# ProPrj_LED__2025-12-14-09-51-38.net
KiCad netlist of a schematic drawn in EasyEDA Pro
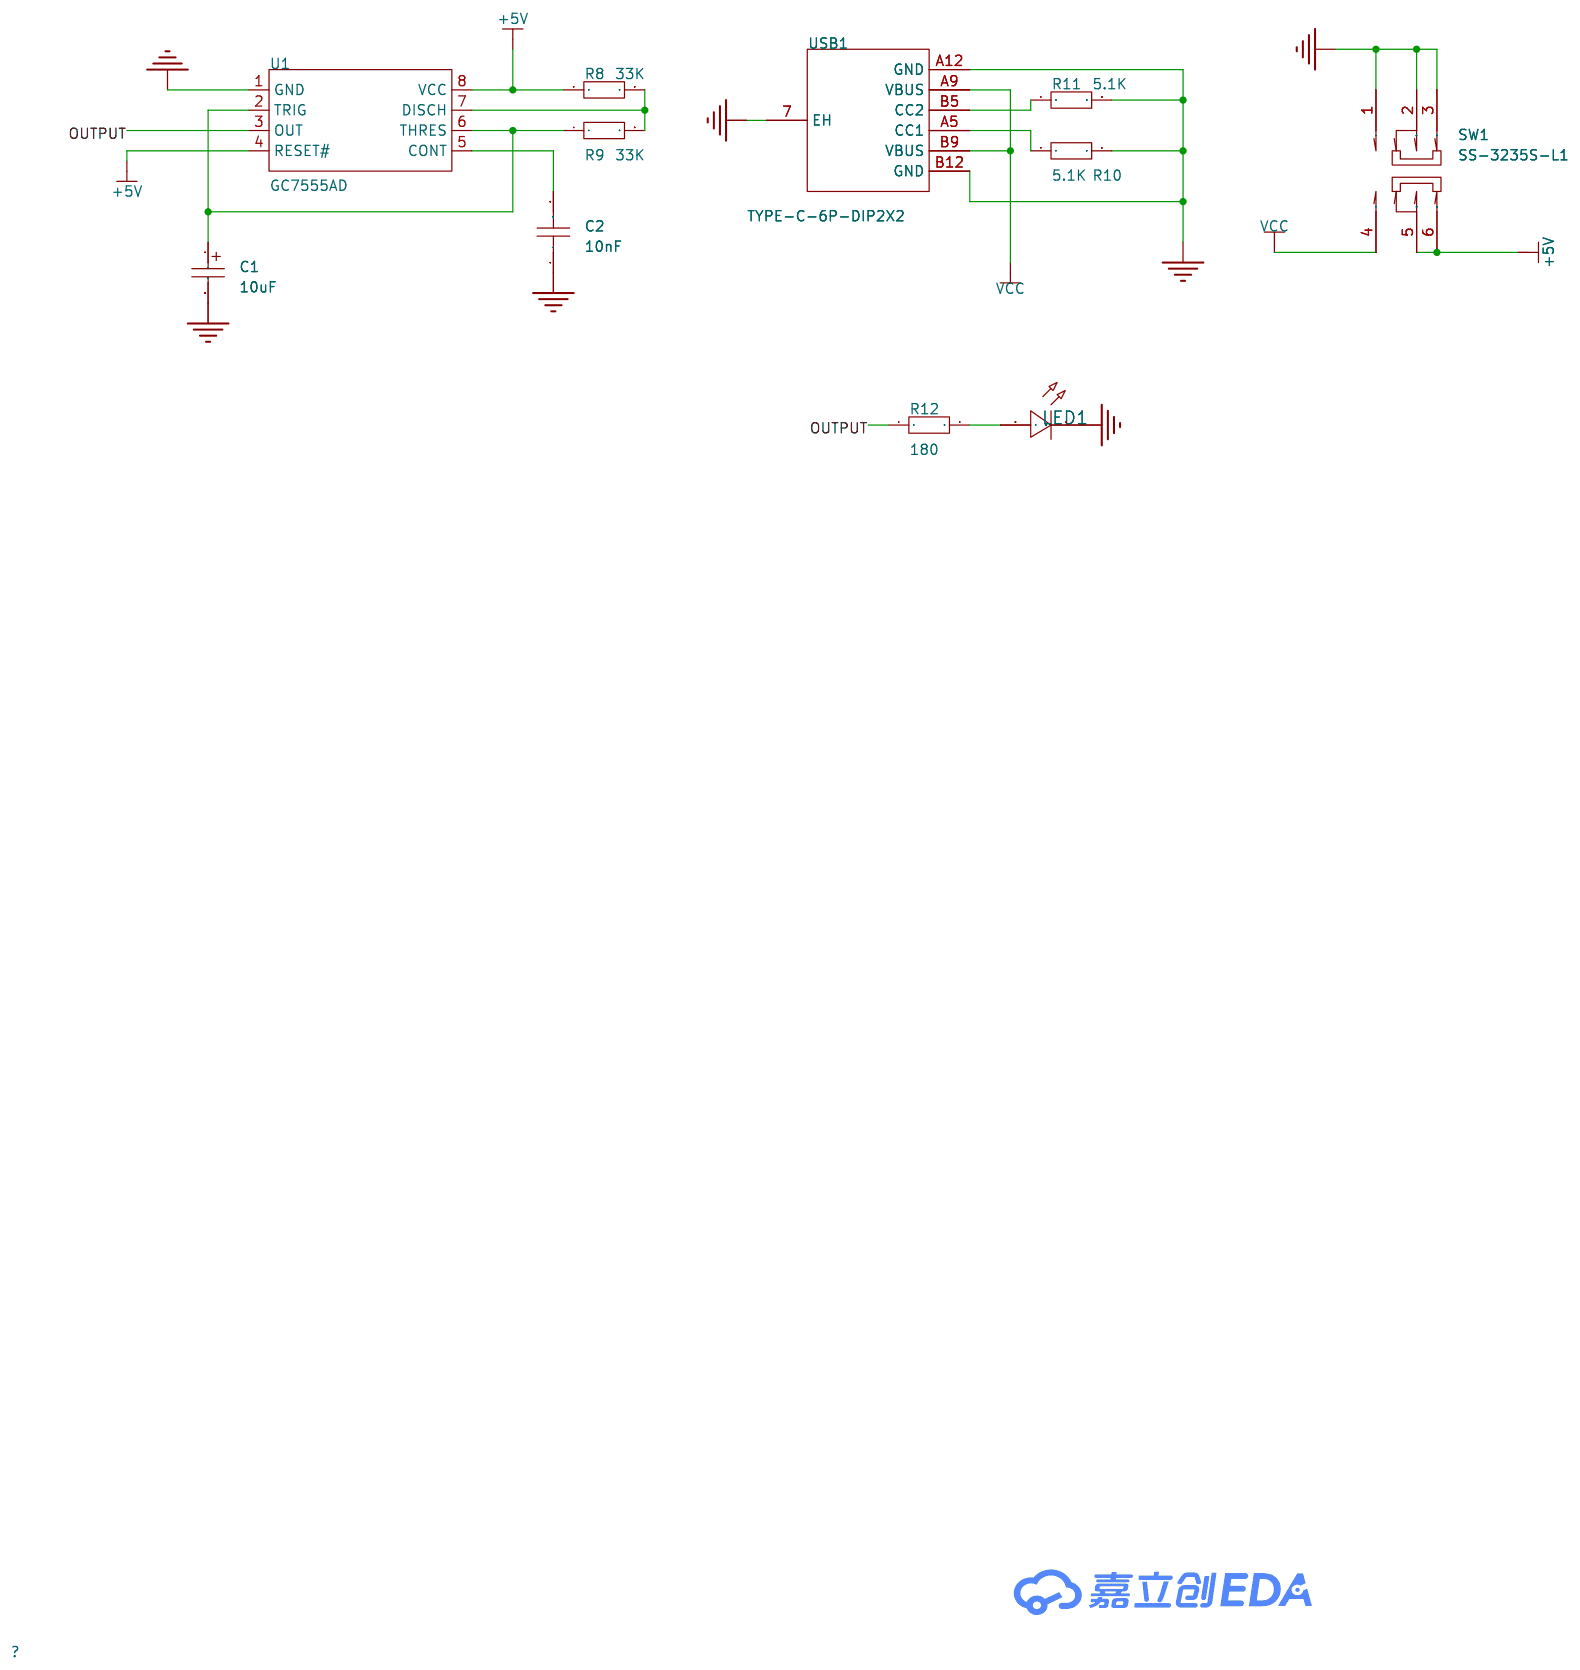
[diagram p0: schematic sheet]

(export (version "E")
  (design (tool "Eeschema 10.0.6"))
  (components
    (comp (ref "C1")
      (value "10uF")
      (footprint "easyedapro:C_Ele_SMD_3x5.4mm")
      (libsource (lib "easyedapro") (part "CAP"))
    )
    (comp (ref "C2")
      (value "10nF")
      (footprint "easyedapro:C0603")
      (libsource (lib "easyedapro") (part "Capacitance"))
    )
    (comp (ref "LED1")
      (value "~")
      (footprint "easyedapro:LED_0603")
      (libsource (lib "easyedapro") (part "LED_R"))
    )
    (comp (ref "R8") (value "33K") (footprint "easyedapro:R0805") (libsource (lib "easyedapro") (part "电阻")))
    (comp (ref "R9") (value "33K") (footprint "easyedapro:R0805") (libsource (lib "easyedapro") (part "电阻")))
    (comp (ref "R10")
      (value "5.1K")
      (footprint "easyedapro:R0805")
      (libsource (lib "easyedapro") (part "电阻"))
    )
    (comp (ref "R11")
      (value "5.1K")
      (footprint "easyedapro:R0805")
      (libsource (lib "easyedapro") (part "电阻"))
    )
    (comp (ref "R12") (value "180") (footprint "easyedapro:R0805") (libsource (lib "easyedapro") (part "电阻")))
    (comp (ref "SW1")
      (value "SS-3235S-L1")
      (footprint "easyedapro:SW-SMD_SS-3235S-LX")
      (description "电路结构:双刀双掷;安装方式:卧贴;开关颜色:黑色;额定电流:50mA;额定电压:12V;工作寿命:1万次;")
      (fields (field (name "Manufacturer") "XKB Connection(中国星坤)"))
      (libsource (lib "easyedapro") (part "SS-3235S-L1"))
    )
    (comp (ref "U1")
      (value "GC7555AD")
      (footprint "easyedapro:PDIP-8_L9.5-W6.4-P2.54-LS7.6-BL")
      (description "通用计时器：时基电路；计时；脉冲产生；满足用户（至少工业级）自主可控的需求。")
      (fields (field (name "Manufacturer") "Sungine(双竞集成)"))
      (libsource (lib "easyedapro") (part "GC7555AD"))
    )
    (comp (ref "USB1")
      (value "TYPE-C-6P-DIP2X2")
      (footprint "easyedapro:TYPE-C-SMD_TYPE-C-6P")
      (libsource (lib "easyedapro") (part "TYPE-C-6P-DIP2X2"))
    )
  )
  (nets
    (net (code "1") (name "+5V") (class "Default")
      (node (ref "R8") (pin "1") (pinfunction "1_1") (pintype "input"))
      (node (ref "SW1") (pin "5") (pinfunction "5_5") (pintype "unspecified"))
      (node (ref "SW1") (pin "6") (pinfunction "6_6") (pintype "unspecified"))
      (node (ref "U1") (pin "4") (pinfunction "RESET#_4") (pintype "unspecified"))
      (node (ref "U1") (pin "8") (pinfunction "VCC_8") (pintype "unspecified"))
    )
    (net (code "2") (name "/OUTPUT") (class "Default")
      (node (ref "R12") (pin "1") (pinfunction "1_1") (pintype "input"))
      (node (ref "U1") (pin "3") (pinfunction "OUT_3") (pintype "unspecified"))
    )
    (net (code "3") (name "GND") (class "Default")
      (node (ref "C1") (pin "2") (pinfunction "2_2") (pintype "input"))
      (node (ref "C2") (pin "1") (pinfunction "1_1") (pintype "input"))
      (node (ref "LED1") (pin "1") (pinfunction "C_1") (pintype "input"))
      (node (ref "R10") (pin "2") (pinfunction "2_2") (pintype "input"))
      (node (ref "R11") (pin "2") (pinfunction "2_2") (pintype "input"))
      (node (ref "SW1") (pin "1") (pinfunction "1_1") (pintype "unspecified"))
      (node (ref "SW1") (pin "2") (pinfunction "2_2") (pintype "unspecified"))
      (node (ref "SW1") (pin "3") (pinfunction "3_3") (pintype "unspecified"))
      (node (ref "U1") (pin "1") (pinfunction "GND_1") (pintype "unspecified"))
      (node (ref "USB1") (pin "7") (pinfunction "EH_7") (pintype "unspecified"))
      (node (ref "USB1") (pin "A12") (pinfunction "GND_A12") (pintype "unspecified"))
      (node (ref "USB1") (pin "B12") (pinfunction "GND_B12") (pintype "unspecified"))
    )
    (net (code "4") (name "Net-(LED1-A)") (class "Default")
      (node (ref "LED1") (pin "2") (pinfunction "A_2") (pintype "input"))
      (node (ref "R12") (pin "2") (pinfunction "2_2") (pintype "input"))
    )
    (net (code "5") (name "Net-(U1-CONT)") (class "Default")
      (node (ref "C2") (pin "2") (pinfunction "2_2") (pintype "input"))
      (node (ref "U1") (pin "5") (pinfunction "CONT_5") (pintype "unspecified"))
    )
    (net (code "6") (name "Net-(U1-DISCH)") (class "Default")
      (node (ref "R8") (pin "2") (pinfunction "2_2") (pintype "input"))
      (node (ref "R9") (pin "2") (pinfunction "2_2") (pintype "input"))
      (node (ref "U1") (pin "7") (pinfunction "DISCH_7") (pintype "unspecified"))
    )
    (net (code "7") (name "Net-(U1-THRES)") (class "Default")
      (node (ref "C1") (pin "1") (pinfunction "1_1") (pintype "input"))
      (node (ref "R9") (pin "1") (pinfunction "1_1") (pintype "input"))
      (node (ref "U1") (pin "2") (pinfunction "TRIG_2") (pintype "unspecified"))
      (node (ref "U1") (pin "6") (pinfunction "THRES_6") (pintype "unspecified"))
    )
    (net (code "8") (name "Net-(USB1-CC1)") (class "Default")
      (node (ref "R10") (pin "1") (pinfunction "1_1") (pintype "input"))
      (node (ref "USB1") (pin "A5") (pinfunction "CC1_A5") (pintype "unspecified"))
    )
    (net (code "9") (name "Net-(USB1-CC2)") (class "Default")
      (node (ref "R11") (pin "1") (pinfunction "1_1") (pintype "input"))
      (node (ref "USB1") (pin "B5") (pinfunction "CC2_B5") (pintype "unspecified"))
    )
    (net (code "10") (name "VCC") (class "Default")
      (node (ref "SW1") (pin "4") (pinfunction "4_4") (pintype "unspecified"))
      (node (ref "USB1") (pin "A9") (pinfunction "VBUS_A9") (pintype "unspecified"))
      (node (ref "USB1") (pin "B9") (pinfunction "VBUS_B9") (pintype "unspecified"))
    )
  )
)
